# mcu.net
KiCad netlist of a schematic drawn in Altium Designer
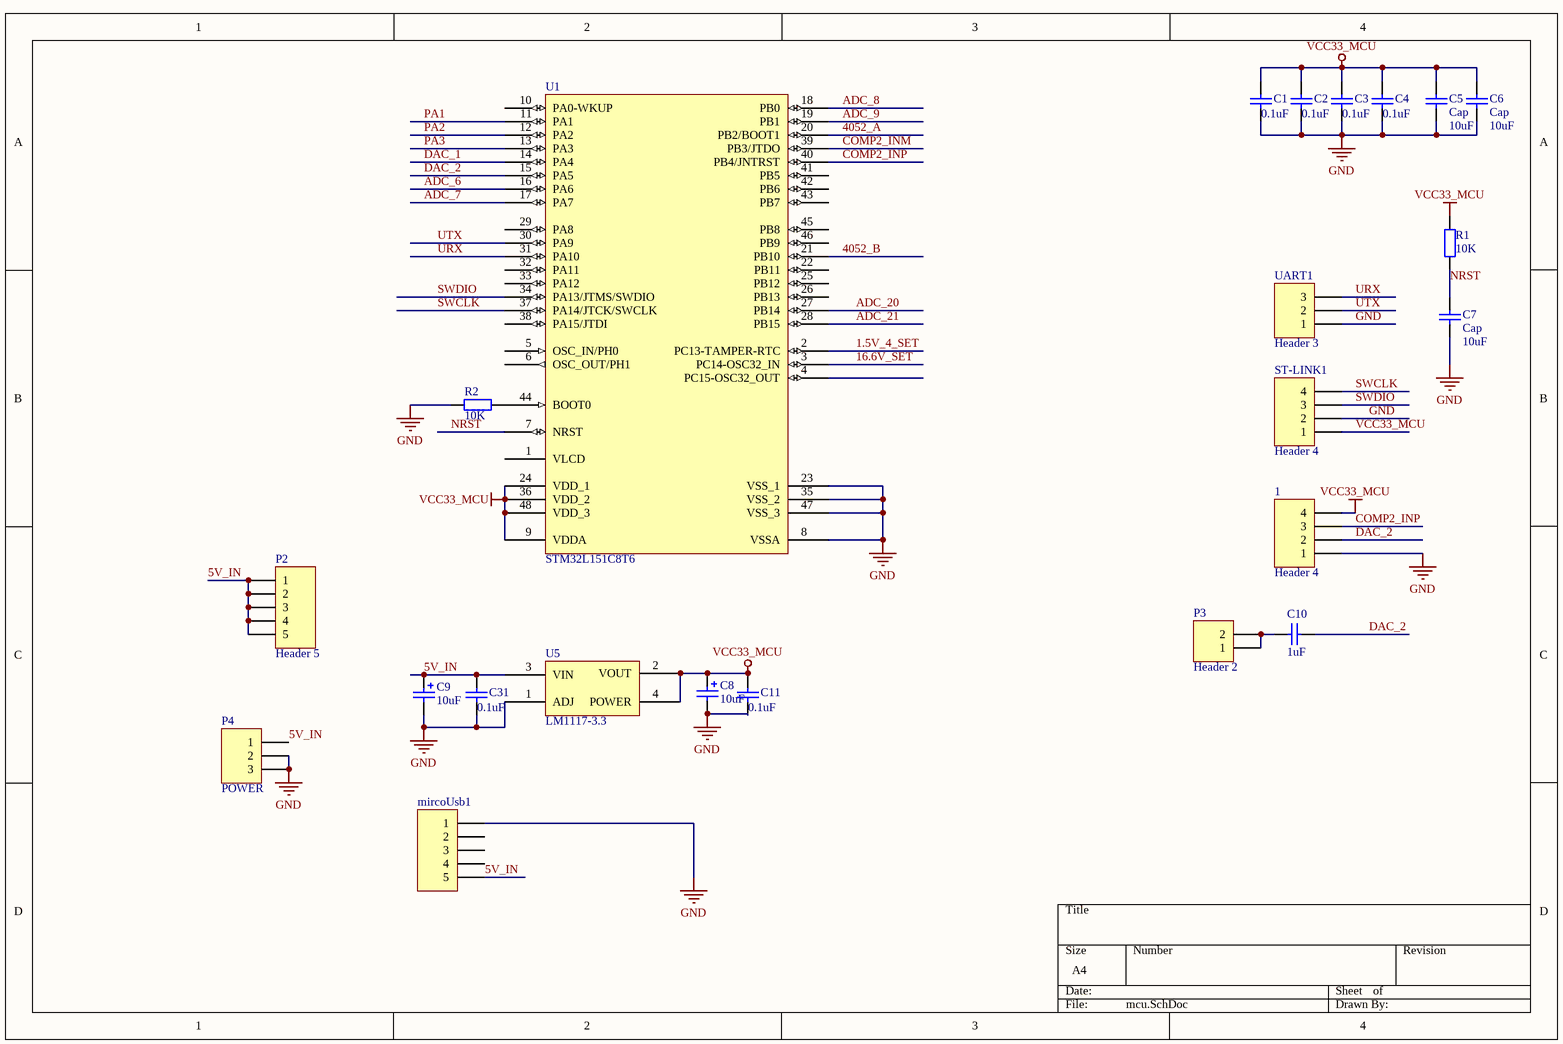
[diagram p0: mcu.SchDoc]

(export (version "E")
  (design (tool "Eeschema 10.0.6"))
  (components
    (comp (ref "1")
      (value "Header 4")
      (footprint "HDR1X4")
      (description "Header, 4-Pin")
      (fields (field (name "PUBLISHER") "Altium Limited"))
      (libsource (lib "Miscellaneous Connectors") (part "Header 4"))
    )
    (comp (ref "C1")
      (value "0.1uF")
      (footprint "c0805")
      (description "Capacitor")
      (fields (field (name "Comment") "Cap") (field (name "PUBLISHER") "Altium Limited"))
      (libsource (lib "Miscellaneous Devices") (part "Cap"))
    )
    (comp (ref "C2")
      (value "0.1uF")
      (footprint "c0805")
      (description "Capacitor")
      (fields (field (name "Comment") "Cap") (field (name "PUBLISHER") "Altium Limited"))
      (libsource (lib "Miscellaneous Devices") (part "Cap"))
    )
    (comp (ref "C3")
      (value "0.1uF")
      (footprint "c0805")
      (description "Capacitor")
      (fields (field (name "Comment") "Cap") (field (name "PUBLISHER") "Altium Limited"))
      (libsource (lib "Miscellaneous Devices") (part "Cap"))
    )
    (comp (ref "C4")
      (value "0.1uF")
      (footprint "c0805")
      (description "Capacitor")
      (fields (field (name "Comment") "Cap") (field (name "PUBLISHER") "Altium Limited"))
      (libsource (lib "Miscellaneous Devices") (part "Cap"))
    )
    (comp (ref "C5")
      (value "Cap")
      (footprint "c0805")
      (description "Capacitor")
      (fields (field (name "ALTIUM_VALUE") "10uF") (field (name "PUBLISHER") "Altium Limited"))
      (libsource (lib "Miscellaneous Devices") (part "Cap"))
    )
    (comp (ref "C6")
      (value "Cap")
      (footprint "c0805")
      (description "Capacitor")
      (fields (field (name "ALTIUM_VALUE") "10uF") (field (name "PUBLISHER") "Altium Limited"))
      (libsource (lib "Miscellaneous Devices") (part "Cap"))
    )
    (comp (ref "C7")
      (value "Cap")
      (footprint "c0805")
      (description "Capacitor")
      (fields (field (name "ALTIUM_VALUE") "10uF") (field (name "PUBLISHER") "Altium Limited"))
      (libsource (lib "Miscellaneous Devices") (part "Cap"))
    )
    (comp (ref "C8")
      (value "10uF")
      (footprint "C1206")
      (description "Polarized Capacitor (Axial)")
      (fields (field (name "Comment") "Cap Pol2") (field (name "PUBLISHER") "Altium Limited"))
      (libsource (lib "Miscellaneous Devices") (part "Cap Pol2"))
    )
    (comp (ref "C9")
      (value "10uF")
      (footprint "C1206")
      (description "Polarized Capacitor (Axial)")
      (fields (field (name "Comment") "Cap Pol2") (field (name "PUBLISHER") "Altium Limited"))
      (libsource (lib "Miscellaneous Devices") (part "Cap Pol2"))
    )
    (comp (ref "C10")
      (value "1uF")
      (footprint "0805")
      (description "Capacitor")
      (fields (field (name "Comment") "Cap") (field (name "PUBLISHER") "Altium Limited"))
      (libsource (lib "Miscellaneous Devices") (part "Cap"))
    )
    (comp (ref "C11")
      (value "0.1uF")
      (footprint "0805")
      (description "Capacitor")
      (fields (field (name "Comment") "Cap") (field (name "PUBLISHER") "Altium Limited"))
      (libsource (lib "Miscellaneous Devices") (part "Cap"))
    )
    (comp (ref "C31")
      (value "0.1uF")
      (footprint "0805")
      (description "Capacitor")
      (fields (field (name "Comment") "Cap") (field (name "PUBLISHER") "Altium Limited"))
      (libsource (lib "Miscellaneous Devices") (part "Cap"))
    )
    (comp (ref "mircoUsb1")
      (value "~")
      (footprint "Micro_USB")
      (description "Header, 5-Pin")
      (fields (field (name "PUBLISHER") "Altium Limited"))
      (libsource (lib "Miscellaneous Connectors") (part "Header 5"))
    )
    (comp (ref "P2")
      (value "Header 5")
      (footprint "HDR1X5")
      (description "Header, 5-Pin")
      (fields (field (name "PUBLISHER") "Altium Limited"))
      (libsource (lib "") (part "Header 5_1"))
    )
    (comp (ref "P3")
      (value "Header 2")
      (footprint "HDR1X2")
      (description "Header, 2-Pin")
      (fields (field (name "PUBLISHER") "Altium Limited"))
      (libsource (lib "Miscellaneous Connectors") (part "Header 2"))
    )
    (comp (ref "P4") (value "POWER") (footprint "POWER_PLUG") (libsource (lib "myschlib") (part "POWER")))
    (comp (ref "R1")
      (value "10K")
      (footprint "0805")
      (description "Resistor")
      (fields (field (name "Comment") "Res2") (field (name "PUBLISHER") "Altium Limited"))
      (libsource (lib "") (part "Res2_1"))
    )
    (comp (ref "R2")
      (value "10K")
      (footprint "0805")
      (description "Resistor")
      (fields (field (name "Comment") "Res2") (field (name "PUBLISHER") "Altium Limited"))
      (libsource (lib "Miscellaneous Devices") (part "Res2"))
    )
    (comp (ref "ST-LINK1")
      (value "Header 4")
      (footprint "HDR1X4")
      (description "Header, 4-Pin")
      (fields (field (name "PUBLISHER") "Altium Limited"))
      (libsource (lib "Miscellaneous Connectors") (part "Header 4"))
    )
    (comp (ref "U1")
      (value "STM32L151C8T6")
      (footprint "LQFP48_N")
      (description "STM32 ARM-based 32-bit MCU with 64 Kbytes Flash, 48-pin LQFP, Industrial Temperature")
      (fields (field (name "PUBLISHER") "Altium Limited"))
      (libsource (lib "ST Microcontroller 32-Bit STM32") (part "STM32L151C8T6"))
    )
    (comp (ref "U5")
      (value "LM1117-3.3")
      (footprint "SOT223")
      (libsource (lib "STM32F407") (part "LM1117-3.3"))
    )
    (comp (ref "UART1")
      (value "Header 3")
      (footprint "HDR1X3")
      (description "Header, 3-Pin")
      (fields (field (name "PUBLISHER") "Altium Limited"))
      (libsource (lib "Miscellaneous Connectors") (part "Header 3"))
    )
  )
  (nets
    (net (code "1") (name "/1.5V_4_SET") (class "Default")
      (node (ref "U1") (pin "2") (pinfunction "PC13-TAMPER-RTC_2") (pintype "bidirectional"))
    )
    (net (code "2") (name "/5V_IN") (class "Default")
      (node (ref "C31") (pin "2") (pinfunction "2_2") (pintype "passive"))
      (node (ref "C9") (pin "1") (pinfunction "1_1") (pintype "passive"))
      (node (ref "P2") (pin "1") (pinfunction "1_1") (pintype "passive"))
      (node (ref "P2") (pin "2") (pinfunction "2_2") (pintype "passive"))
      (node (ref "P2") (pin "3") (pinfunction "3_3") (pintype "passive"))
      (node (ref "P2") (pin "4") (pinfunction "4_4") (pintype "passive"))
      (node (ref "P2") (pin "5") (pinfunction "5_5") (pintype "passive"))
      (node (ref "P4") (pin "1") (pinfunction "1_1") (pintype "passive"))
      (node (ref "U5") (pin "3") (pinfunction "VIN_3") (pintype "passive"))
      (node (ref "mircoUsb1") (pin "5") (pinfunction "5_5") (pintype "passive"))
    )
    (net (code "3") (name "/16.6V_SET") (class "Default")
      (node (ref "U1") (pin "3") (pinfunction "PC14-OSC32_IN_3") (pintype "bidirectional"))
    )
    (net (code "4") (name "/4052_A") (class "Default")
      (node (ref "U1") (pin "20") (pinfunction "PB2/BOOT1_20") (pintype "bidirectional"))
    )
    (net (code "5") (name "/4052_B") (class "Default")
      (node (ref "U1") (pin "21") (pinfunction "PB10_21") (pintype "bidirectional"))
    )
    (net (code "6") (name "/ADC_6") (class "Default")
      (node (ref "U1") (pin "16") (pinfunction "PA6_16") (pintype "bidirectional"))
    )
    (net (code "7") (name "/ADC_7") (class "Default")
      (node (ref "U1") (pin "17") (pinfunction "PA7_17") (pintype "bidirectional"))
    )
    (net (code "8") (name "/ADC_8") (class "Default")
      (node (ref "U1") (pin "18") (pinfunction "PB0_18") (pintype "bidirectional"))
    )
    (net (code "9") (name "/ADC_9") (class "Default")
      (node (ref "U1") (pin "19") (pinfunction "PB1_19") (pintype "bidirectional"))
    )
    (net (code "10") (name "/ADC_20") (class "Default")
      (node (ref "U1") (pin "27") (pinfunction "PB14_27") (pintype "bidirectional"))
    )
    (net (code "11") (name "/ADC_21") (class "Default")
      (node (ref "U1") (pin "28") (pinfunction "PB15_28") (pintype "bidirectional"))
    )
    (net (code "12") (name "/COMP2_INM") (class "Default")
      (node (ref "U1") (pin "39") (pinfunction "PB3/JTDO_39") (pintype "bidirectional"))
    )
    (net (code "13") (name "/COMP2_INP") (class "Default")
      (node (ref "1") (pin "3") (pinfunction "3_3") (pintype "passive"))
      (node (ref "U1") (pin "40") (pinfunction "PB4/JNTRST_40") (pintype "bidirectional"))
    )
    (net (code "14") (name "/DAC_1") (class "Default")
      (node (ref "U1") (pin "14") (pinfunction "PA4_14") (pintype "bidirectional"))
    )
    (net (code "15") (name "/DAC_2") (class "Default")
      (node (ref "1") (pin "2") (pinfunction "2_2") (pintype "passive"))
      (node (ref "C10") (pin "1") (pinfunction "1_1") (pintype "passive"))
      (node (ref "U1") (pin "15") (pinfunction "PA5_15") (pintype "bidirectional"))
    )
    (net (code "16") (name "/NRST") (class "Default")
      (node (ref "C7") (pin "2") (pinfunction "2_2") (pintype "passive"))
      (node (ref "R1") (pin "2") (pinfunction "2_2") (pintype "passive"))
      (node (ref "U1") (pin "7") (pinfunction "NRST_7") (pintype "bidirectional"))
    )
    (net (code "17") (name "/PA1") (class "Default")
      (node (ref "U1") (pin "11") (pinfunction "PA1_11") (pintype "bidirectional"))
    )
    (net (code "18") (name "/PA2") (class "Default")
      (node (ref "U1") (pin "12") (pinfunction "PA2_12") (pintype "bidirectional"))
    )
    (net (code "19") (name "/PA3") (class "Default")
      (node (ref "U1") (pin "13") (pinfunction "PA3_13") (pintype "bidirectional"))
    )
    (net (code "20") (name "/SWCLK") (class "Default")
      (node (ref "ST-LINK1") (pin "4") (pinfunction "4_4") (pintype "passive"))
      (node (ref "U1") (pin "37") (pinfunction "PA14/JTCK/SWCLK_37") (pintype "bidirectional"))
    )
    (net (code "21") (name "/SWDIO") (class "Default")
      (node (ref "ST-LINK1") (pin "3") (pinfunction "3_3") (pintype "passive"))
      (node (ref "U1") (pin "34") (pinfunction "PA13/JTMS/SWDIO_34") (pintype "bidirectional"))
    )
    (net (code "22") (name "/URX") (class "Default")
      (node (ref "U1") (pin "31") (pinfunction "PA10_31") (pintype "bidirectional"))
      (node (ref "UART1") (pin "3") (pinfunction "3_3") (pintype "passive"))
    )
    (net (code "23") (name "/UTX") (class "Default")
      (node (ref "U1") (pin "30") (pinfunction "PA9_30") (pintype "bidirectional"))
      (node (ref "UART1") (pin "2") (pinfunction "2_2") (pintype "passive"))
    )
    (net (code "24") (name "GND") (class "Default")
      (node (ref "1") (pin "1") (pinfunction "1_1") (pintype "passive"))
      (node (ref "C1") (pin "1") (pinfunction "1_1") (pintype "passive"))
      (node (ref "C11") (pin "1") (pinfunction "1_1") (pintype "passive"))
      (node (ref "C2") (pin "1") (pinfunction "1_1") (pintype "passive"))
      (node (ref "C3") (pin "1") (pinfunction "1_1") (pintype "passive"))
      (node (ref "C31") (pin "1") (pinfunction "1_1") (pintype "passive"))
      (node (ref "C4") (pin "1") (pinfunction "1_1") (pintype "passive"))
      (node (ref "C5") (pin "1") (pinfunction "1_1") (pintype "passive"))
      (node (ref "C6") (pin "1") (pinfunction "1_1") (pintype "passive"))
      (node (ref "C7") (pin "1") (pinfunction "1_1") (pintype "passive"))
      (node (ref "C8") (pin "2") (pinfunction "2_2") (pintype "passive"))
      (node (ref "C9") (pin "2") (pinfunction "2_2") (pintype "passive"))
      (node (ref "P4") (pin "2") (pinfunction "2_2") (pintype "passive"))
      (node (ref "P4") (pin "3") (pinfunction "3_3") (pintype "passive"))
      (node (ref "R2") (pin "1") (pinfunction "1_1") (pintype "passive"))
      (node (ref "ST-LINK1") (pin "2") (pinfunction "2_2") (pintype "passive"))
      (node (ref "U1") (pin "23") (pinfunction "VSS_1_23") (pintype "power_in"))
      (node (ref "U1") (pin "35") (pinfunction "VSS_2_35") (pintype "power_in"))
      (node (ref "U1") (pin "47") (pinfunction "VSS_3_47") (pintype "power_in"))
      (node (ref "U1") (pin "8") (pinfunction "VSSA_8") (pintype "power_in"))
      (node (ref "U5") (pin "1") (pinfunction "ADJ_1") (pintype "passive"))
      (node (ref "UART1") (pin "1") (pinfunction "1_1") (pintype "passive"))
      (node (ref "mircoUsb1") (pin "1") (pinfunction "1_1") (pintype "passive"))
    )
    (net (code "25") (name "Net-(C10-Pad2)") (class "Default")
      (node (ref "C10") (pin "2") (pinfunction "2_2") (pintype "passive"))
      (node (ref "P3") (pin "1") (pinfunction "1_1") (pintype "passive"))
      (node (ref "P3") (pin "2") (pinfunction "2_2") (pintype "passive"))
    )
    (net (code "26") (name "Net-(U1-BOOT0)") (class "Default")
      (node (ref "R2") (pin "2") (pinfunction "2_2") (pintype "passive"))
      (node (ref "U1") (pin "44") (pinfunction "BOOT0_44") (pintype "input"))
    )
    (net (code "27") (name "VCC33_MCU") (class "Default")
      (node (ref "1") (pin "4") (pinfunction "4_4") (pintype "passive"))
      (node (ref "C1") (pin "2") (pinfunction "2_2") (pintype "passive"))
      (node (ref "C11") (pin "2") (pinfunction "2_2") (pintype "passive"))
      (node (ref "C2") (pin "2") (pinfunction "2_2") (pintype "passive"))
      (node (ref "C3") (pin "2") (pinfunction "2_2") (pintype "passive"))
      (node (ref "C4") (pin "2") (pinfunction "2_2") (pintype "passive"))
      (node (ref "C5") (pin "2") (pinfunction "2_2") (pintype "passive"))
      (node (ref "C6") (pin "2") (pinfunction "2_2") (pintype "passive"))
      (node (ref "C8") (pin "1") (pinfunction "1_1") (pintype "passive"))
      (node (ref "R1") (pin "1") (pinfunction "1_1") (pintype "passive"))
      (node (ref "ST-LINK1") (pin "1") (pinfunction "1_1") (pintype "passive"))
      (node (ref "U1") (pin "24") (pinfunction "VDD_1_24") (pintype "power_in"))
      (node (ref "U1") (pin "36") (pinfunction "VDD_2_36") (pintype "power_in"))
      (node (ref "U1") (pin "48") (pinfunction "VDD_3_48") (pintype "power_in"))
      (node (ref "U1") (pin "9") (pinfunction "VDDA_9") (pintype "power_in"))
      (node (ref "U5") (pin "2") (pinfunction "VOUT_2") (pintype "passive"))
      (node (ref "U5") (pin "4") (pinfunction "POWER_4") (pintype "passive"))
    )
    (net (code "28") (name "unconnected-(U1-OSC_IN{slash}PH0-Pad5)") (class "Default")
      (node (ref "U1") (pin "5") (pinfunction "OSC_IN/PH0_5") (pintype "input"))
    )
    (net (code "29") (name "unconnected-(U1-OSC_OUT{slash}PH1-Pad6)") (class "Default")
      (node (ref "U1") (pin "6") (pinfunction "OSC_OUT/PH1_6") (pintype "output"))
    )
    (net (code "30") (name "unconnected-(U1-PA0-WKUP-Pad10)") (class "Default")
      (node (ref "U1") (pin "10") (pinfunction "PA0-WKUP_10") (pintype "bidirectional"))
    )
    (net (code "31") (name "unconnected-(U1-PA8-Pad29)") (class "Default")
      (node (ref "U1") (pin "29") (pinfunction "PA8_29") (pintype "bidirectional"))
    )
    (net (code "32") (name "unconnected-(U1-PA11-Pad32)") (class "Default")
      (node (ref "U1") (pin "32") (pinfunction "PA11_32") (pintype "bidirectional"))
    )
    (net (code "33") (name "unconnected-(U1-PA12-Pad33)") (class "Default")
      (node (ref "U1") (pin "33") (pinfunction "PA12_33") (pintype "bidirectional"))
    )
    (net (code "34") (name "unconnected-(U1-PA15{slash}JTDI-Pad38)") (class "Default")
      (node (ref "U1") (pin "38") (pinfunction "PA15/JTDI_38") (pintype "bidirectional"))
    )
    (net (code "35") (name "unconnected-(U1-PB5-Pad41)") (class "Default")
      (node (ref "U1") (pin "41") (pinfunction "PB5_41") (pintype "bidirectional"))
    )
    (net (code "36") (name "unconnected-(U1-PB6-Pad42)") (class "Default")
      (node (ref "U1") (pin "42") (pinfunction "PB6_42") (pintype "bidirectional"))
    )
    (net (code "37") (name "unconnected-(U1-PB7-Pad43)") (class "Default")
      (node (ref "U1") (pin "43") (pinfunction "PB7_43") (pintype "bidirectional"))
    )
    (net (code "38") (name "unconnected-(U1-PB8-Pad45)") (class "Default")
      (node (ref "U1") (pin "45") (pinfunction "PB8_45") (pintype "bidirectional"))
    )
    (net (code "39") (name "unconnected-(U1-PB9-Pad46)") (class "Default")
      (node (ref "U1") (pin "46") (pinfunction "PB9_46") (pintype "bidirectional"))
    )
    (net (code "40") (name "unconnected-(U1-PB11-Pad22)") (class "Default")
      (node (ref "U1") (pin "22") (pinfunction "PB11_22") (pintype "bidirectional"))
    )
    (net (code "41") (name "unconnected-(U1-PB12-Pad25)") (class "Default")
      (node (ref "U1") (pin "25") (pinfunction "PB12_25") (pintype "bidirectional"))
    )
    (net (code "42") (name "unconnected-(U1-PB13-Pad26)") (class "Default")
      (node (ref "U1") (pin "26") (pinfunction "PB13_26") (pintype "bidirectional"))
    )
    (net (code "43") (name "unconnected-(U1-PC15-OSC32_OUT-Pad4)") (class "Default")
      (node (ref "U1") (pin "4") (pinfunction "PC15-OSC32_OUT_4") (pintype "bidirectional"))
    )
    (net (code "44") (name "unconnected-(U1-VLCD-Pad1)") (class "Default")
      (node (ref "U1") (pin "1") (pinfunction "VLCD_1") (pintype "power_in"))
    )
    (net (code "45") (name "unconnected-(mircoUsb1-Pad2)") (class "Default")
      (node (ref "mircoUsb1") (pin "2") (pinfunction "2_2") (pintype "passive"))
    )
    (net (code "46") (name "unconnected-(mircoUsb1-Pad3)") (class "Default")
      (node (ref "mircoUsb1") (pin "3") (pinfunction "3_3") (pintype "passive"))
    )
    (net (code "47") (name "unconnected-(mircoUsb1-Pad4)") (class "Default")
      (node (ref "mircoUsb1") (pin "4") (pinfunction "4_4") (pintype "passive"))
    )
  )
)
